# iRat_2_1_Microcontroller.net
KiCad netlist of a schematic drawn in Altium Designer
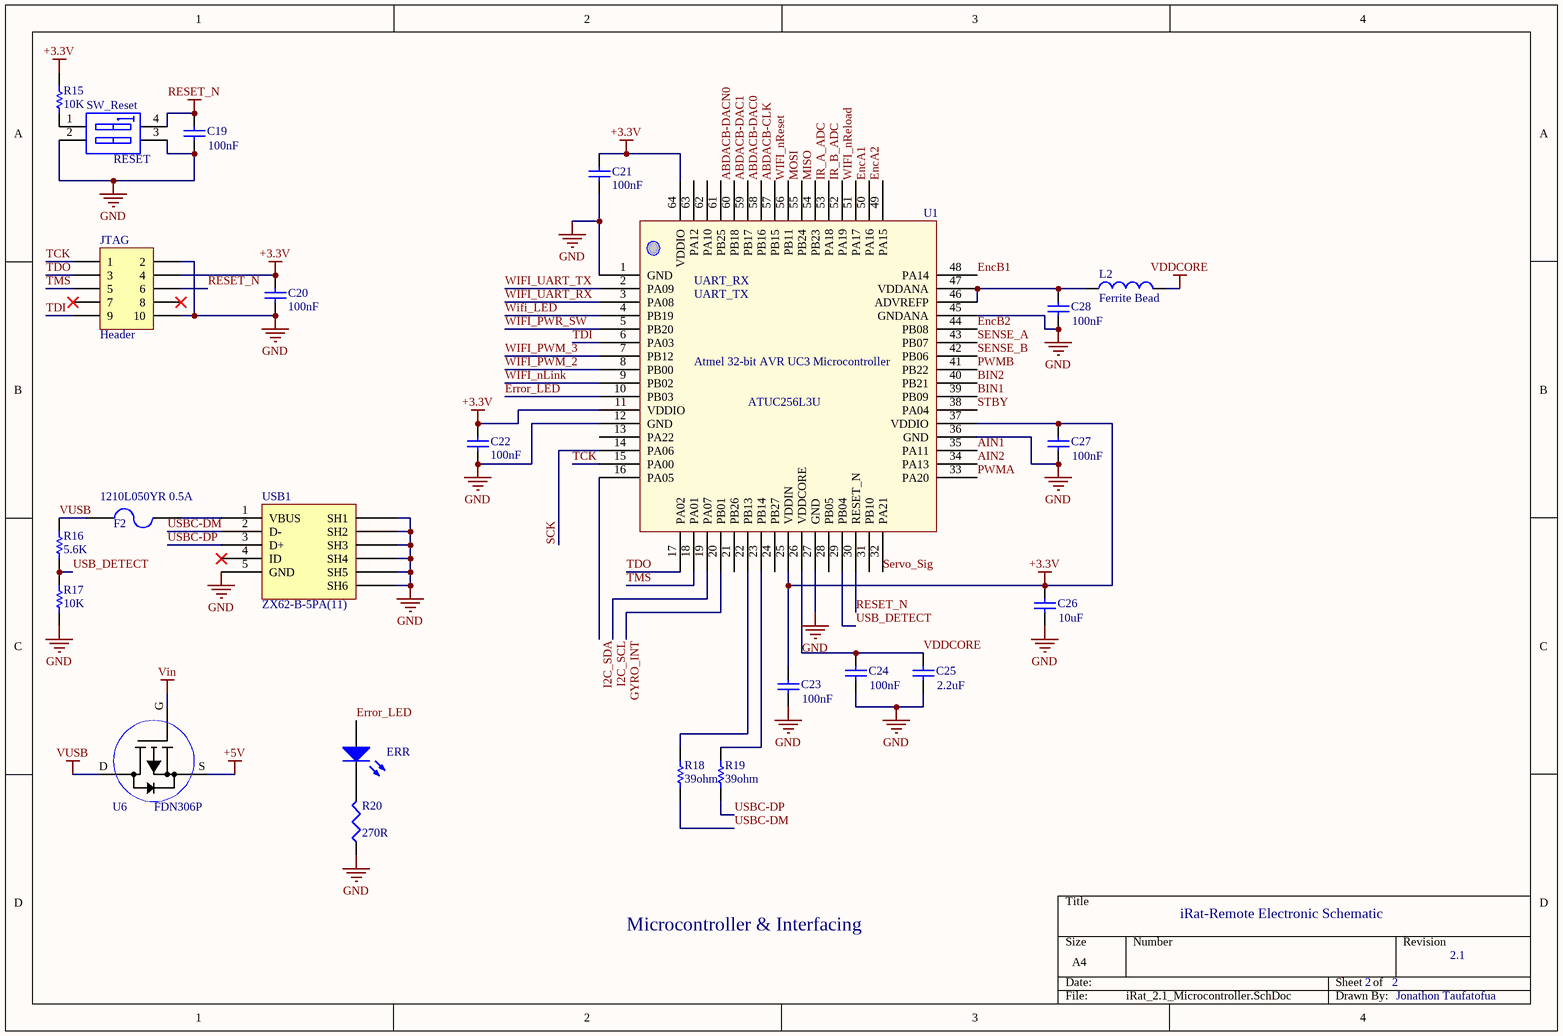
[diagram p0: iRat_2.1_Microcontroller.SchDoc]

(export (version "E")
  (design (tool "Eeschema 10.0.6"))
  (components
    (comp (ref "C19")
      (value "100nF")
      (footprint "1608[0603]")
      (description "Capacitor (Semiconductor SIM Model)")
      (fields (field (name "Comment") "Cap Semi") (field (name "PUBLISHER") "Altium Limited"))
      (libsource (lib "Miscellaneous Devices") (part "Cap Semi"))
    )
    (comp (ref "C20")
      (value "100nF")
      (footprint "1608[0603]")
      (description "Capacitor (Semiconductor SIM Model)")
      (fields (field (name "Comment") "Cap Semi") (field (name "PUBLISHER") "Altium Limited"))
      (libsource (lib "Miscellaneous Devices") (part "Cap Semi"))
    )
    (comp (ref "C21")
      (value "100nF")
      (footprint "1608[0603]")
      (description "Capacitor (Semiconductor SIM Model)")
      (fields (field (name "Comment") "Cap Semi") (field (name "PUBLISHER") "Altium Limited"))
      (libsource (lib "Miscellaneous Devices") (part "Cap Semi"))
    )
    (comp (ref "C22")
      (value "100nF")
      (footprint "1608[0603]")
      (description "Capacitor (Semiconductor SIM Model)")
      (fields (field (name "Comment") "Cap Semi") (field (name "PUBLISHER") "Altium Limited"))
      (libsource (lib "Miscellaneous Devices") (part "Cap Semi"))
    )
    (comp (ref "C23")
      (value "100nF")
      (footprint "1608[0603]")
      (description "Capacitor (Semiconductor SIM Model)")
      (fields (field (name "Comment") "Cap Semi") (field (name "PUBLISHER") "Altium Limited"))
      (libsource (lib "Miscellaneous Devices") (part "Cap Semi"))
    )
    (comp (ref "C24")
      (value "100nF")
      (footprint "1608[0603]")
      (description "Capacitor (Semiconductor SIM Model)")
      (fields (field (name "Comment") "Cap Semi") (field (name "PUBLISHER") "Altium Limited"))
      (libsource (lib "Miscellaneous Devices") (part "Cap Semi"))
    )
    (comp (ref "C25")
      (value "2.2uF")
      (footprint "C1206")
      (description "Capacitor (Semiconductor SIM Model)")
      (fields (field (name "Comment") "Cap Semi") (field (name "PUBLISHER") "Altium Limited"))
      (libsource (lib "Miscellaneous Devices") (part "Cap Semi"))
    )
    (comp (ref "C26")
      (value "10uF")
      (footprint "C1206")
      (description "Capacitor (Semiconductor SIM Model)")
      (fields (field (name "PUBLISHER") "Altium Limited"))
      (libsource (lib "Miscellaneous Devices") (part "Cap Semi"))
    )
    (comp (ref "C27")
      (value "100nF")
      (footprint "1608[0603]")
      (description "Capacitor (Semiconductor SIM Model)")
      (fields (field (name "Comment") "Cap Semi") (field (name "PUBLISHER") "Altium Limited"))
      (libsource (lib "Miscellaneous Devices") (part "Cap Semi"))
    )
    (comp (ref "C28")
      (value "100nF")
      (footprint "1608[0603]")
      (description "Capacitor (Semiconductor SIM Model)")
      (fields (field (name "Comment") "Cap Semi") (field (name "PUBLISHER") "Altium Limited"))
      (libsource (lib "Miscellaneous Devices") (part "Cap Semi"))
    )
    (comp (ref "ERR")
      (value "LNJ347W83RA")
      (footprint "0402-A")
      (description "GREEN Wifi LED")
      (fields (field (name "PUBLISHER") "Altium Limited"))
      (libsource (lib "Miscellaneous Devices") (part "LED2"))
    )
    (comp (ref "F2")
      (value "1210L050YR 0.5A")
      (footprint "14-1210")
      (description "Fuse")
      (fields (field (name "PUBLISHER") "Altium Limited"))
      (libsource (lib "Miscellaneous Devices") (part "Fuse 2"))
    )
    (comp (ref "JTAG")
      (value "Header")
      (footprint "HDR2X5")
      (description "Header, 5-Pin, Dual row")
      (fields (field (name "PUBLISHER") "Altium Limited"))
      (libsource (lib "Miscellaneous Connectors") (part "Header 5X2"))
    )
    (comp (ref "L2")
      (value "Ferrite Bead")
      (footprint "0805E")
      (description "MLS0805-4S7-301")
      (fields (field (name "PUBLISHER") "Altium Limited"))
      (libsource (lib "Miscellaneous Devices") (part "Inductor"))
    )
    (comp (ref "R15")
      (value "10K")
      (footprint "0402")
      (description "Semiconductor Resistor")
      (fields (field (name "PUBLISHER") "Altium Limited"))
      (libsource (lib "Miscellaneous Devices") (part "Res Semi"))
    )
    (comp (ref "R16")
      (value "5.6K")
      (footprint "0402")
      (description "Semiconductor Resistor")
      (fields (field (name "Comment") "Res Semi") (field (name "PUBLISHER") "Altium Limited"))
      (libsource (lib "Miscellaneous Devices") (part "Res Semi"))
    )
    (comp (ref "R17")
      (value "10K")
      (footprint "0402")
      (description "Semiconductor Resistor")
      (fields (field (name "Comment") "Res Semi") (field (name "PUBLISHER") "Altium Limited"))
      (libsource (lib "Miscellaneous Devices") (part "Res Semi"))
    )
    (comp (ref "R18")
      (value "39ohm")
      (footprint "0603E")
      (description "Resistor")
      (fields (field (name "Comment") "Res1") (field (name "PUBLISHER") "Altium Limited"))
      (libsource (lib "Miscellaneous Devices") (part "Res1"))
    )
    (comp (ref "R19")
      (value "39ohm")
      (footprint "0603E")
      (description "Resistor")
      (fields (field (name "Comment") "Res1") (field (name "PUBLISHER") "Altium Limited"))
      (libsource (lib "Miscellaneous Devices") (part "Res1"))
    )
    (comp (ref "R20")
      (value "270R")
      (footprint "0402")
      (description "Resistor")
      (fields (field (name "Comment") "Res3") (field (name "PUBLISHER") "Altium Limited"))
      (libsource (lib "Miscellaneous Devices") (part "Res3"))
    )
    (comp (ref "SW_Reset")
      (value "RESET")
      (footprint "SW16")
      (description "DIP Switch, 2 Position, SPST")
      (fields (field (name "PUBLISHER") "Altium Limited"))
      (libsource (lib "Miscellaneous Devices") (part "SW DIP-2"))
    )
    (comp (ref "U1")
      (value "ATUC256L3U-AUT")
      (footprint "TQFP64_M")
      (description "Atmel 32-bit AVR UC3 Microcontroller")
      (libsource (lib "iRat_2.0") (part "ATUC256L3U-AUT"))
    )
    (comp (ref "U6") (value "FDN306P") (footprint "FDN306P") (libsource (lib "iRat_2.0") (part "FDN306P")))
    (comp (ref "USB1")
      (value "ZX62-B-5PA(11)")
      (footprint "ZX62-B-5PA(11)")
      (description "Micro-B USB Receptacle")
      (libsource (lib "iRat_2.0") (part "ZX62-B-5PA(11)"))
    )
  )
  (nets
    (net (code "1") (name "+3.3V") (class "Default")
      (node (ref "C20") (pin "1") (pinfunction "1_1") (pintype "passive"))
      (node (ref "C21") (pin "2") (pinfunction "2_2") (pintype "passive"))
      (node (ref "C22") (pin "2") (pinfunction "2_2") (pintype "passive"))
      (node (ref "C23") (pin "2") (pinfunction "2_2") (pintype "passive"))
      (node (ref "C26") (pin "2") (pinfunction "2_2") (pintype "passive"))
      (node (ref "C27") (pin "2") (pinfunction "2_2") (pintype "passive"))
      (node (ref "JTAG") (pin "4") (pinfunction "4_4") (pintype "passive"))
      (node (ref "R15") (pin "1") (pinfunction "1_1") (pintype "passive"))
      (node (ref "U1") (pin "11") (pinfunction "VDDIO_11") (pintype "passive"))
      (node (ref "U1") (pin "25") (pinfunction "VDDIN_25") (pintype "passive"))
      (node (ref "U1") (pin "37") (pinfunction "VDDIO_37") (pintype "passive"))
      (node (ref "U1") (pin "64") (pinfunction "VDDIO_64") (pintype "passive"))
    )
    (net (code "2") (name "+5V") (class "Default")
      (node (ref "U6") (pin "S") (pinfunction "3_S") (pintype "passive"))
    )
    (net (code "3") (name "/ABDACB-CLK") (class "Default")
      (node (ref "U1") (pin "57") (pinfunction "PB15_57") (pintype "passive"))
    )
    (net (code "4") (name "/ABDACB-DAC0") (class "Default")
      (node (ref "U1") (pin "58") (pinfunction "PB16_58") (pintype "passive"))
    )
    (net (code "5") (name "/ABDACB-DAC1") (class "Default")
      (node (ref "U1") (pin "59") (pinfunction "PB17_59") (pintype "passive"))
    )
    (net (code "6") (name "/ABDACB-DACN0") (class "Default")
      (node (ref "U1") (pin "60") (pinfunction "PB18_60") (pintype "passive"))
    )
    (net (code "7") (name "/AIN1") (class "Default")
      (node (ref "U1") (pin "35") (pinfunction "PA11_35") (pintype "passive"))
    )
    (net (code "8") (name "/AIN2") (class "Default")
      (node (ref "U1") (pin "34") (pinfunction "PA13_34") (pintype "passive"))
    )
    (net (code "9") (name "/BIN1") (class "Default")
      (node (ref "U1") (pin "39") (pinfunction "PB09_39") (pintype "passive"))
    )
    (net (code "10") (name "/BIN2") (class "Default")
      (node (ref "U1") (pin "40") (pinfunction "PB21_40") (pintype "passive"))
    )
    (net (code "11") (name "/EncA1") (class "Default")
      (node (ref "U1") (pin "50") (pinfunction "PA16_50") (pintype "passive"))
    )
    (net (code "12") (name "/EncA2") (class "Default")
      (node (ref "U1") (pin "49") (pinfunction "PA15_49") (pintype "passive"))
    )
    (net (code "13") (name "/EncB1") (class "Default")
      (node (ref "U1") (pin "48") (pinfunction "PA14_48") (pintype "passive"))
    )
    (net (code "14") (name "/EncB2") (class "Default")
      (node (ref "U1") (pin "44") (pinfunction "PB08_44") (pintype "passive"))
    )
    (net (code "15") (name "/Error_LED") (class "Default")
      (node (ref "ERR") (pin "1") (pinfunction "A_1") (pintype "passive"))
      (node (ref "U1") (pin "10") (pinfunction "PB03_10") (pintype "passive"))
    )
    (net (code "16") (name "/GYRO_INT") (class "Default")
      (node (ref "U1") (pin "20") (pinfunction "PB01_20") (pintype "passive"))
    )
    (net (code "17") (name "/I2C_SCL") (class "Default")
      (node (ref "U1") (pin "19") (pinfunction "PA07_19") (pintype "passive"))
    )
    (net (code "18") (name "/I2C_SDA") (class "Default")
      (node (ref "U1") (pin "16") (pinfunction "PA05_16") (pintype "passive"))
    )
    (net (code "19") (name "/IR_A_ADC") (class "Default")
      (node (ref "U1") (pin "53") (pinfunction "PA18_53") (pintype "passive"))
    )
    (net (code "20") (name "/IR_B_ADC") (class "Default")
      (node (ref "U1") (pin "52") (pinfunction "PA19_52") (pintype "passive"))
    )
    (net (code "21") (name "/MISO") (class "Default")
      (node (ref "U1") (pin "54") (pinfunction "PB23_54") (pintype "passive"))
    )
    (net (code "22") (name "/MOSI") (class "Default")
      (node (ref "U1") (pin "55") (pinfunction "PB24_55") (pintype "passive"))
    )
    (net (code "23") (name "/PWMA") (class "Default")
      (node (ref "U1") (pin "33") (pinfunction "PA20_33") (pintype "passive"))
    )
    (net (code "24") (name "/PWMB") (class "Default")
      (node (ref "U1") (pin "41") (pinfunction "PB22_41") (pintype "passive"))
    )
    (net (code "25") (name "/SCK") (class "Default")
      (node (ref "U1") (pin "14") (pinfunction "PA06_14") (pintype "passive"))
    )
    (net (code "26") (name "/SENSE_A") (class "Default")
      (node (ref "U1") (pin "43") (pinfunction "PB07_43") (pintype "passive"))
    )
    (net (code "27") (name "/SENSE_B") (class "Default")
      (node (ref "U1") (pin "42") (pinfunction "PB06_42") (pintype "passive"))
    )
    (net (code "28") (name "/STBY") (class "Default")
      (node (ref "U1") (pin "38") (pinfunction "PA04_38") (pintype "passive"))
    )
    (net (code "29") (name "/Servo_Sig") (class "Default")
      (node (ref "U1") (pin "32") (pinfunction "PA21_32") (pintype "passive"))
    )
    (net (code "30") (name "/TCK") (class "Default")
      (node (ref "JTAG") (pin "1") (pinfunction "1_1") (pintype "passive"))
      (node (ref "U1") (pin "15") (pinfunction "PA00_15") (pintype "passive"))
    )
    (net (code "31") (name "/TDI") (class "Default")
      (node (ref "JTAG") (pin "9") (pinfunction "9_9") (pintype "passive"))
      (node (ref "U1") (pin "6") (pinfunction "PA03_6") (pintype "passive"))
    )
    (net (code "32") (name "/TDO") (class "Default")
      (node (ref "JTAG") (pin "3") (pinfunction "3_3") (pintype "passive"))
      (node (ref "U1") (pin "17") (pinfunction "PA02_17") (pintype "passive"))
    )
    (net (code "33") (name "/TMS") (class "Default")
      (node (ref "JTAG") (pin "5") (pinfunction "5_5") (pintype "passive"))
      (node (ref "U1") (pin "18") (pinfunction "PA01_18") (pintype "passive"))
    )
    (net (code "34") (name "/USBC-DM") (class "Default")
      (node (ref "R18") (pin "2") (pinfunction "2_2") (pintype "passive"))
      (node (ref "USB1") (pin "2") (pinfunction "D-_2") (pintype "passive"))
    )
    (net (code "35") (name "/USBC-DP") (class "Default")
      (node (ref "R19") (pin "2") (pinfunction "2_2") (pintype "passive"))
      (node (ref "USB1") (pin "3") (pinfunction "D+_3") (pintype "passive"))
    )
    (net (code "36") (name "/USB_DETECT") (class "Default")
      (node (ref "R16") (pin "1") (pinfunction "1_1") (pintype "passive"))
      (node (ref "R17") (pin "2") (pinfunction "2_2") (pintype "passive"))
      (node (ref "U1") (pin "29") (pinfunction "PB04_29") (pintype "passive"))
    )
    (net (code "37") (name "/WIFI_PWM_2") (class "Default")
      (node (ref "U1") (pin "8") (pinfunction "PB00_8") (pintype "passive"))
    )
    (net (code "38") (name "/WIFI_PWM_3") (class "Default")
      (node (ref "U1") (pin "7") (pinfunction "PB12_7") (pintype "passive"))
    )
    (net (code "39") (name "/WIFI_PWR_SW") (class "Default")
      (node (ref "U1") (pin "5") (pinfunction "PB20_5") (pintype "passive"))
    )
    (net (code "40") (name "/WIFI_UART_RX") (class "Default")
      (node (ref "U1") (pin "3") (pinfunction "PA08_3") (pintype "passive"))
    )
    (net (code "41") (name "/WIFI_UART_TX") (class "Default")
      (node (ref "U1") (pin "2") (pinfunction "PA09_2") (pintype "passive"))
    )
    (net (code "42") (name "/WIFI_nLink") (class "Default")
      (node (ref "U1") (pin "9") (pinfunction "PB02_9") (pintype "passive"))
    )
    (net (code "43") (name "/WIFI_nReload") (class "Default")
      (node (ref "U1") (pin "51") (pinfunction "PA17_51") (pintype "passive"))
    )
    (net (code "44") (name "/WIFI_nReset") (class "Default")
      (node (ref "U1") (pin "56") (pinfunction "PB11_56") (pintype "passive"))
    )
    (net (code "45") (name "/Wifi_LED") (class "Default")
      (node (ref "U1") (pin "4") (pinfunction "PB19_4") (pintype "passive"))
    )
    (net (code "46") (name "GND") (class "Default")
      (node (ref "C19") (pin "1") (pinfunction "1_1") (pintype "passive"))
      (node (ref "C20") (pin "2") (pinfunction "2_2") (pintype "passive"))
      (node (ref "C21") (pin "1") (pinfunction "1_1") (pintype "passive"))
      (node (ref "C22") (pin "1") (pinfunction "1_1") (pintype "passive"))
      (node (ref "C23") (pin "1") (pinfunction "1_1") (pintype "passive"))
      (node (ref "C24") (pin "1") (pinfunction "1_1") (pintype "passive"))
      (node (ref "C25") (pin "1") (pinfunction "1_1") (pintype "passive"))
      (node (ref "C26") (pin "1") (pinfunction "1_1") (pintype "passive"))
      (node (ref "C27") (pin "1") (pinfunction "1_1") (pintype "passive"))
      (node (ref "C28") (pin "1") (pinfunction "1_1") (pintype "passive"))
      (node (ref "JTAG") (pin "10") (pinfunction "10_10") (pintype "passive"))
      (node (ref "JTAG") (pin "2") (pinfunction "2_2") (pintype "passive"))
      (node (ref "R17") (pin "1") (pinfunction "1_1") (pintype "passive"))
      (node (ref "R20") (pin "1") (pinfunction "1_1") (pintype "passive"))
      (node (ref "SW_Reset") (pin "2") (pinfunction "2_2") (pintype "passive"))
      (node (ref "SW_Reset") (pin "3") (pinfunction "2_3") (pintype "passive"))
      (node (ref "U1") (pin "1") (pinfunction "GND_1") (pintype "passive"))
      (node (ref "U1") (pin "12") (pinfunction "GND_12") (pintype "passive"))
      (node (ref "U1") (pin "27") (pinfunction "GND_27") (pintype "passive"))
      (node (ref "U1") (pin "36") (pinfunction "GND_36") (pintype "passive"))
      (node (ref "U1") (pin "45") (pinfunction "GNDANA_45") (pintype "passive"))
      (node (ref "USB1") (pin "5") (pinfunction "GND_5") (pintype "passive"))
      (node (ref "USB1") (pin "SH1") (pinfunction "SH1_SH1") (pintype "passive"))
      (node (ref "USB1") (pin "SH2") (pinfunction "SH2_SH2") (pintype "passive"))
      (node (ref "USB1") (pin "SH3") (pinfunction "SH3_SH3") (pintype "passive"))
      (node (ref "USB1") (pin "SH4") (pinfunction "SH4_SH4") (pintype "passive"))
      (node (ref "USB1") (pin "SH5") (pinfunction "SH5_SH5") (pintype "passive"))
      (node (ref "USB1") (pin "SH6") (pinfunction "SH6_SH6") (pintype "passive"))
    )
    (net (code "47") (name "Net-(ERR-K)") (class "Default")
      (node (ref "ERR") (pin "2") (pinfunction "K_2") (pintype "passive"))
      (node (ref "R20") (pin "2") (pinfunction "2_2") (pintype "passive"))
    )
    (net (code "48") (name "Net-(R15-Pad2)") (class "Default")
      (node (ref "R15") (pin "2") (pinfunction "2_2") (pintype "passive"))
      (node (ref "SW_Reset") (pin "1") (pinfunction "1_1") (pintype "passive"))
    )
    (net (code "49") (name "Net-(U1-ADVREFP)") (class "Default")
      (node (ref "C28") (pin "2") (pinfunction "2_2") (pintype "passive"))
      (node (ref "L2") (pin "1") (pinfunction "1_1") (pintype "passive"))
      (node (ref "U1") (pin "46") (pinfunction "ADVREFP_46") (pintype "passive"))
      (node (ref "U1") (pin "47") (pinfunction "VDDANA_47") (pintype "passive"))
    )
    (net (code "50") (name "Net-(U1-PB13)") (class "Default")
      (node (ref "R18") (pin "1") (pinfunction "1_1") (pintype "passive"))
      (node (ref "U1") (pin "22") (pinfunction "PB13_22") (pintype "passive"))
    )
    (net (code "51") (name "Net-(U1-PB14)") (class "Default")
      (node (ref "R19") (pin "1") (pinfunction "1_1") (pintype "passive"))
      (node (ref "U1") (pin "23") (pinfunction "PB14_23") (pintype "passive"))
    )
    (net (code "52") (name "Net-(USB1-VBUS)") (class "Default")
      (node (ref "F2") (pin "1") (pinfunction "1_1") (pintype "passive"))
      (node (ref "USB1") (pin "1") (pinfunction "VBUS_1") (pintype "passive"))
    )
    (net (code "53") (name "RESET_N") (class "Default")
      (node (ref "C19") (pin "2") (pinfunction "2_2") (pintype "passive"))
      (node (ref "JTAG") (pin "6") (pinfunction "6_6") (pintype "passive"))
      (node (ref "SW_Reset") (pin "4") (pinfunction "1_4") (pintype "passive"))
      (node (ref "U1") (pin "30") (pinfunction "RESET_N_30") (pintype "passive"))
    )
    (net (code "54") (name "VDDCORE") (class "Default")
      (node (ref "C24") (pin "2") (pinfunction "2_2") (pintype "passive"))
      (node (ref "C25") (pin "2") (pinfunction "2_2") (pintype "passive"))
      (node (ref "L2") (pin "2") (pinfunction "2_2") (pintype "passive"))
      (node (ref "U1") (pin "26") (pinfunction "VDDCORE_26") (pintype "passive"))
    )
    (net (code "55") (name "VUSB") (class "Default")
      (node (ref "F2") (pin "2") (pinfunction "2_2") (pintype "passive"))
      (node (ref "R16") (pin "2") (pinfunction "2_2") (pintype "passive"))
      (node (ref "U6") (pin "D") (pinfunction "D_D") (pintype "passive"))
    )
    (net (code "56") (name "Vin") (class "Default")
      (node (ref "U6") (pin "G") (pinfunction "G_G") (pintype "passive"))
    )
    (net (code "57") (name "unconnected-(JTAG-Pad7)") (class "Default")
      (node (ref "JTAG") (pin "7") (pinfunction "7_7") (pintype "passive+no_connect"))
    )
    (net (code "58") (name "unconnected-(JTAG-Pad8)") (class "Default")
      (node (ref "JTAG") (pin "8") (pinfunction "8_8") (pintype "passive+no_connect"))
    )
    (net (code "59") (name "unconnected-(U1-PA10-Pad62)") (class "Default")
      (node (ref "U1") (pin "62") (pinfunction "PA10_62") (pintype "passive"))
    )
    (net (code "60") (name "unconnected-(U1-PA12-Pad63)") (class "Default")
      (node (ref "U1") (pin "63") (pinfunction "PA12_63") (pintype "passive"))
    )
    (net (code "61") (name "unconnected-(U1-PA22-Pad13)") (class "Default")
      (node (ref "U1") (pin "13") (pinfunction "PA22_13") (pintype "passive"))
    )
    (net (code "62") (name "unconnected-(U1-PB05-Pad28)") (class "Default")
      (node (ref "U1") (pin "28") (pinfunction "PB05_28") (pintype "passive"))
    )
    (net (code "63") (name "unconnected-(U1-PB10-Pad31)") (class "Default")
      (node (ref "U1") (pin "31") (pinfunction "PB10_31") (pintype "passive"))
    )
    (net (code "64") (name "unconnected-(U1-PB25-Pad61)") (class "Default")
      (node (ref "U1") (pin "61") (pinfunction "PB25_61") (pintype "passive"))
    )
    (net (code "65") (name "unconnected-(U1-PB26-Pad21)") (class "Default")
      (node (ref "U1") (pin "21") (pinfunction "PB26_21") (pintype "passive"))
    )
    (net (code "66") (name "unconnected-(U1-PB27-Pad24)") (class "Default")
      (node (ref "U1") (pin "24") (pinfunction "PB27_24") (pintype "passive"))
    )
    (net (code "67") (name "unconnected-(USB1-ID-Pad4)") (class "Default")
      (node (ref "USB1") (pin "4") (pinfunction "ID_4") (pintype "passive+no_connect"))
    )
  )
)
